# KA2_5.net
KiCad netlist of a schematic drawn in Altium Designer
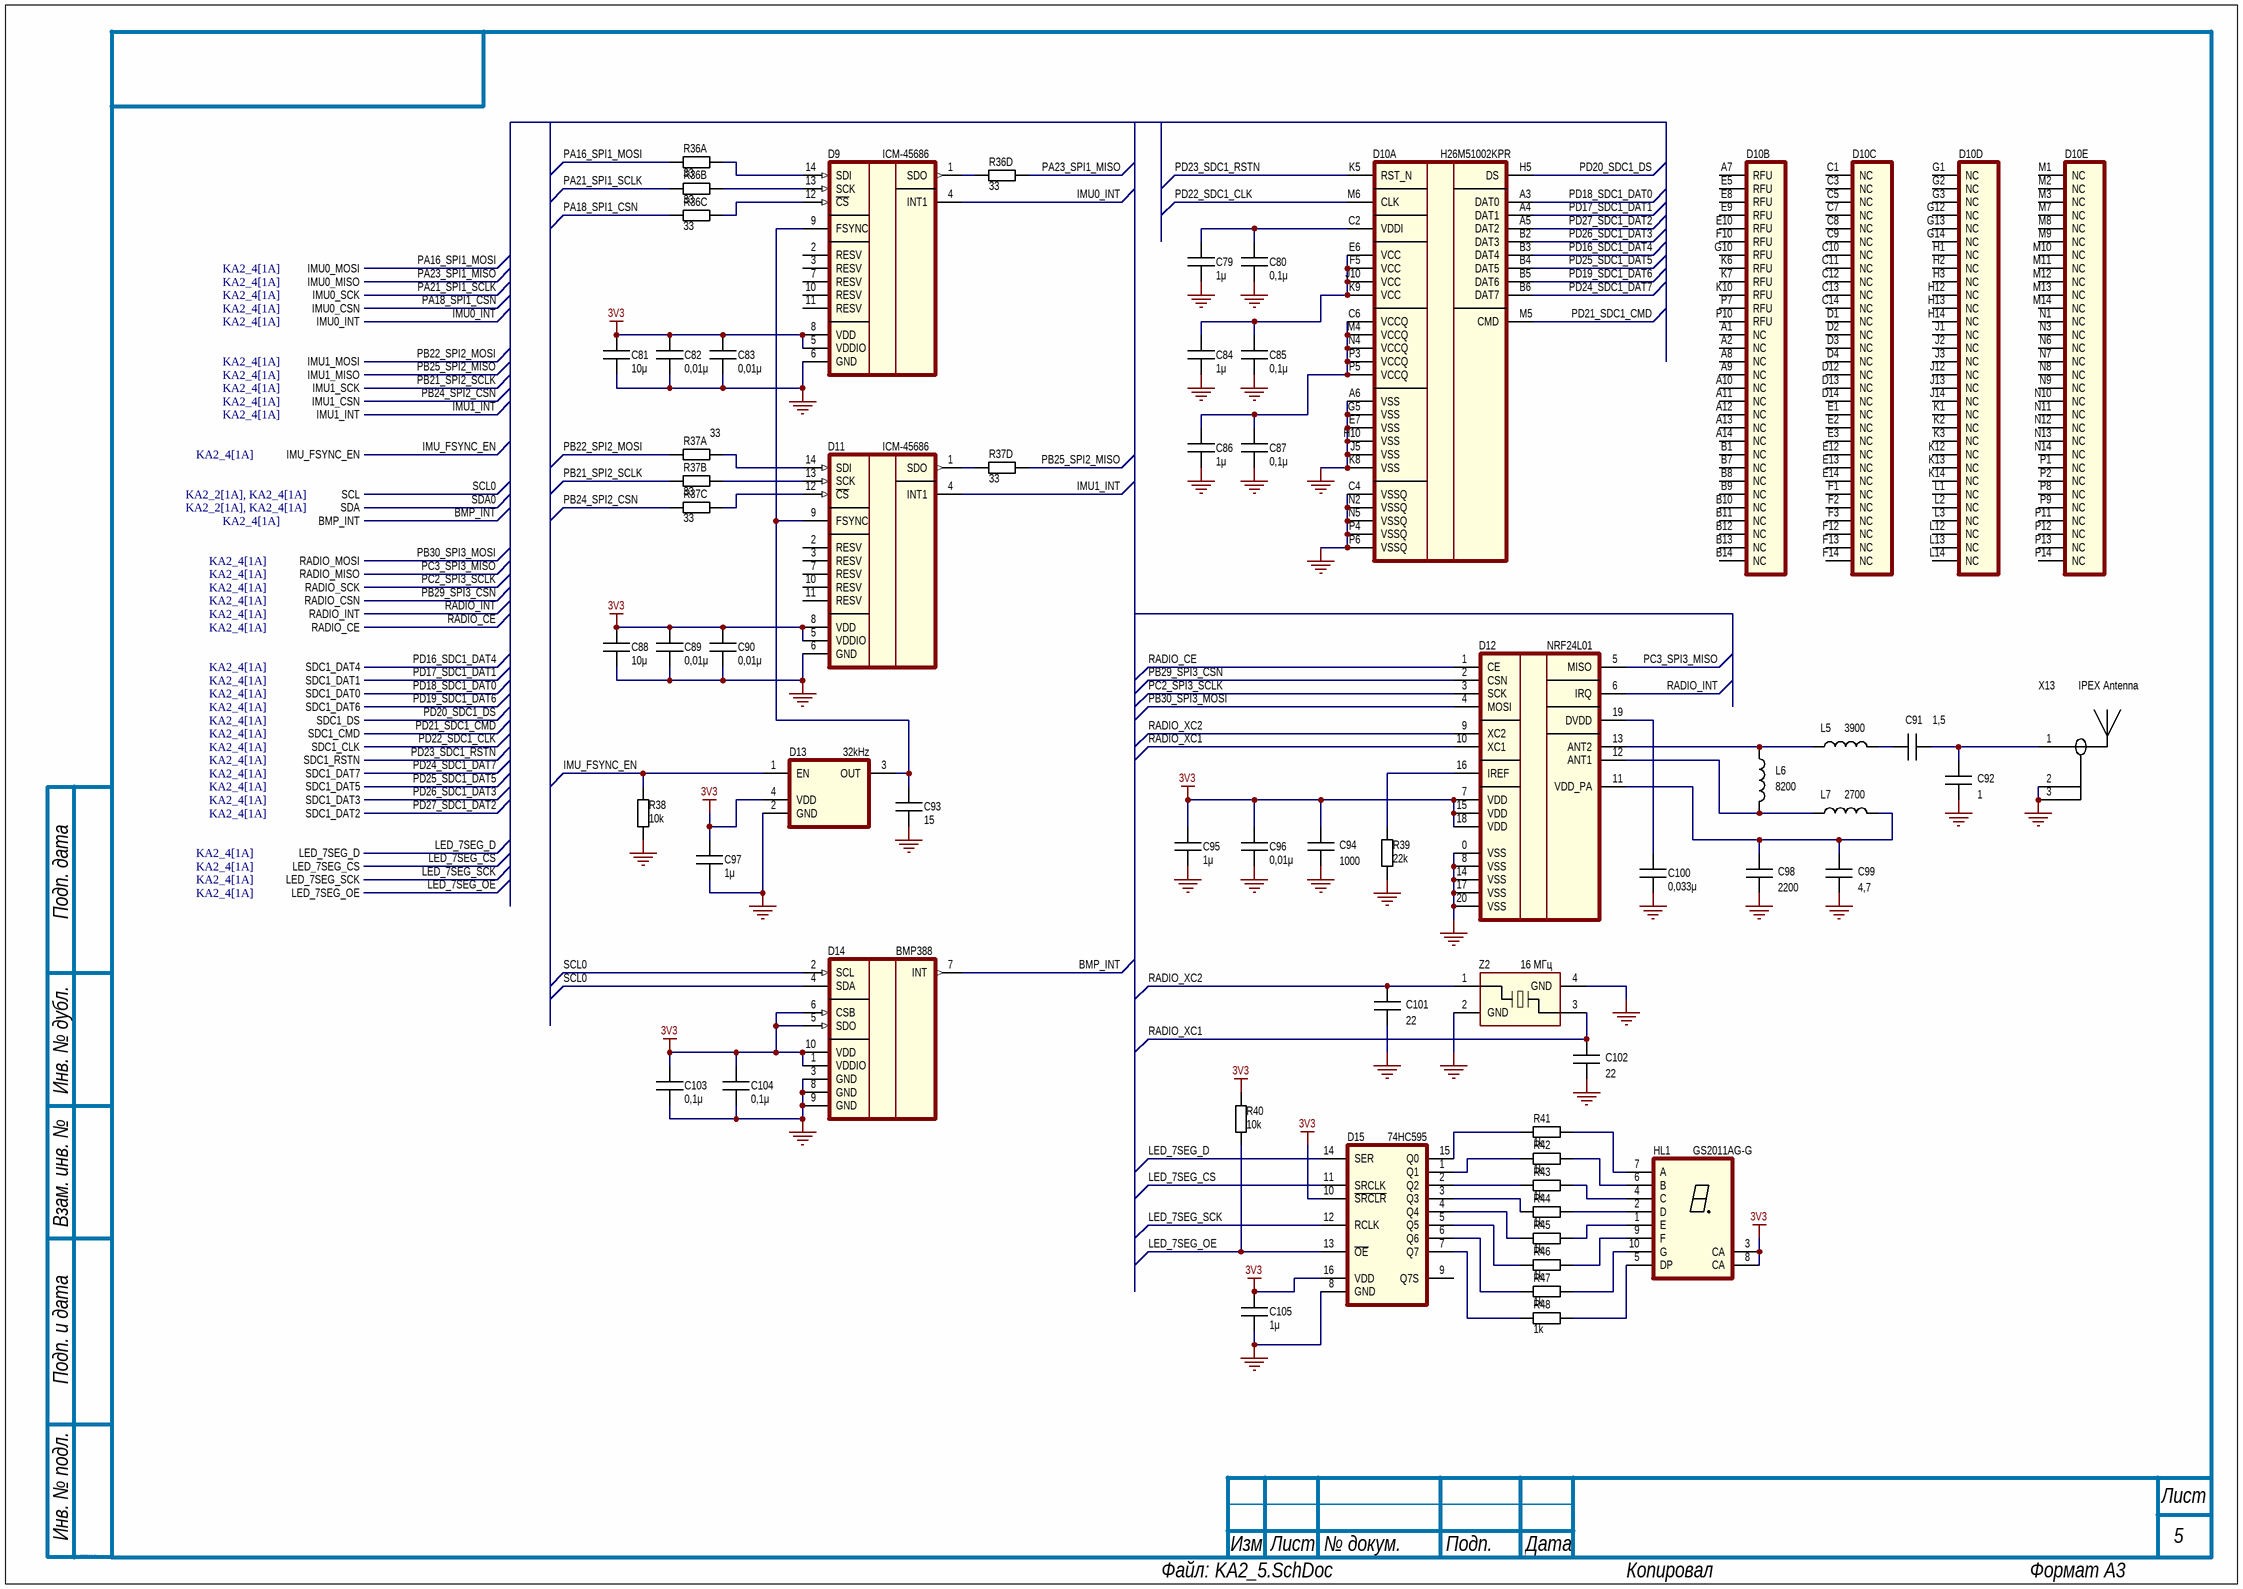
[diagram p0: KA2_5.SchDoc]

(export (version "E")
  (design (tool "Eeschema 10.0.6"))
  (components
    (comp (ref "C79")
      (value "1μ")
      (footprint "Capacitor_0402")
      (fields
        (field (name "VALUEMANUFACTURERPARTNUMBER") "Ceramic capacitor, 1μ, X7R, ±10%, 16V, 0402")
        (field (name "TOLERANCE") "±10%")
        (field (name "VOLTAGE") "16V")
      )
      (libsource (lib "Barsotion") (part "Ceramic_0402"))
    )
    (comp (ref "C80")
      (value "0,1μ")
      (footprint "Capacitor_0402")
      (fields
        (field (name "VALUEMANUFACTURERPARTNUMBER") "Ceramic capacitor, 0,1μ, X7R, ±10%, 16V, 0402")
        (field (name "TOLERANCE") "±10%")
        (field (name "VOLTAGE") "16V")
      )
      (libsource (lib "Barsotion") (part "Ceramic_0402"))
    )
    (comp (ref "C81")
      (value "10μ")
      (footprint "Capacitor_0402")
      (fields
        (field (name "VALUEMANUFACTURERPARTNUMBER") "Ceramic capacitor, 10μ, X7R, ±10%, 16V, 0402")
        (field (name "TOLERANCE") "±10%")
        (field (name "VOLTAGE") "16V")
      )
      (libsource (lib "Barsotion") (part "Ceramic_0402"))
    )
    (comp (ref "C82")
      (value "0,01μ")
      (footprint "Capacitor_0402")
      (fields
        (field (name "VALUEMANUFACTURERPARTNUMBER") "Ceramic capacitor, 0,01μ, X7R, ±10%, 16V, 0402")
        (field (name "TOLERANCE") "±10%")
        (field (name "VOLTAGE") "16V")
      )
      (libsource (lib "Barsotion") (part "Ceramic_0402"))
    )
    (comp (ref "C83")
      (value "0,01μ")
      (footprint "Capacitor_0402")
      (fields
        (field (name "VALUEMANUFACTURERPARTNUMBER") "Ceramic capacitor, 0,01μ, X7R, ±10%, 16V, 0402")
        (field (name "TOLERANCE") "±10%")
        (field (name "VOLTAGE") "16V")
      )
      (libsource (lib "Barsotion") (part "Ceramic_0402"))
    )
    (comp (ref "C84")
      (value "1μ")
      (footprint "Capacitor_0402")
      (fields
        (field (name "VALUEMANUFACTURERPARTNUMBER") "Ceramic capacitor, 1μ, X7R, ±10%, 16V, 0402")
        (field (name "TOLERANCE") "±10%")
        (field (name "VOLTAGE") "16V")
      )
      (libsource (lib "Barsotion") (part "Ceramic_0402"))
    )
    (comp (ref "C85")
      (value "0,1μ")
      (footprint "Capacitor_0402")
      (fields
        (field (name "VALUEMANUFACTURERPARTNUMBER") "Ceramic capacitor, 0,1μ, X7R, ±10%, 16V, 0402")
        (field (name "TOLERANCE") "±10%")
        (field (name "VOLTAGE") "16V")
      )
      (libsource (lib "Barsotion") (part "Ceramic_0402"))
    )
    (comp (ref "C86")
      (value "1μ")
      (footprint "Capacitor_0402")
      (fields
        (field (name "VALUEMANUFACTURERPARTNUMBER") "Ceramic capacitor, 1μ, X7R, ±10%, 16V, 0402")
        (field (name "TOLERANCE") "±10%")
        (field (name "VOLTAGE") "16V")
      )
      (libsource (lib "Barsotion") (part "Ceramic_0402"))
    )
    (comp (ref "C87")
      (value "0,1μ")
      (footprint "Capacitor_0402")
      (fields
        (field (name "VALUEMANUFACTURERPARTNUMBER") "Ceramic capacitor, 0,1μ, X7R, ±10%, 16V, 0402")
        (field (name "TOLERANCE") "±10%")
        (field (name "VOLTAGE") "16V")
      )
      (libsource (lib "Barsotion") (part "Ceramic_0402"))
    )
    (comp (ref "C88")
      (value "10μ")
      (footprint "Capacitor_0402")
      (fields
        (field (name "VALUEMANUFACTURERPARTNUMBER") "Ceramic capacitor, 10μ, X7R, ±10%, 16V, 0402")
        (field (name "TOLERANCE") "±10%")
        (field (name "VOLTAGE") "16V")
      )
      (libsource (lib "Barsotion") (part "Ceramic_0402"))
    )
    (comp (ref "C89")
      (value "0,01μ")
      (footprint "Capacitor_0402")
      (fields
        (field (name "VALUEMANUFACTURERPARTNUMBER") "Ceramic capacitor, 0,01μ, X7R, ±10%, 16V, 0402")
        (field (name "TOLERANCE") "±10%")
        (field (name "VOLTAGE") "16V")
      )
      (libsource (lib "Barsotion") (part "Ceramic_0402"))
    )
    (comp (ref "C90")
      (value "0,01μ")
      (footprint "Capacitor_0402")
      (fields
        (field (name "VALUEMANUFACTURERPARTNUMBER") "Ceramic capacitor, 0,01μ, X7R, ±10%, 16V, 0402")
        (field (name "TOLERANCE") "±10%")
        (field (name "VOLTAGE") "16V")
      )
      (libsource (lib "Barsotion") (part "Ceramic_0402"))
    )
    (comp (ref "C91")
      (value "1,5")
      (footprint "Capacitor_0402")
      (fields
        (field (name "VALUEMANUFACTURERPARTNUMBER") "Ceramic capacitor, 1,5, X7R, ±10%, 16V, 0402")
        (field (name "TOLERANCE") "±10%")
        (field (name "VOLTAGE") "16V")
      )
      (libsource (lib "Barsotion") (part "Ceramic_0402"))
    )
    (comp (ref "C92")
      (value "1")
      (footprint "Capacitor_0402")
      (fields
        (field (name "VALUEMANUFACTURERPARTNUMBER") "Ceramic capacitor, 1, X7R, ±10%, 16V, 0402")
        (field (name "TOLERANCE") "±10%")
        (field (name "VOLTAGE") "16V")
      )
      (libsource (lib "Barsotion") (part "Ceramic_0402"))
    )
    (comp (ref "C93")
      (value "15")
      (footprint "Capacitor_0402")
      (fields
        (field (name "VALUEMANUFACTURERPARTNUMBER") "Ceramic capacitor, 15, X7R, ±10%, 16V, 0402")
        (field (name "TOLERANCE") "±10%")
        (field (name "VOLTAGE") "16V")
      )
      (libsource (lib "Barsotion") (part "Ceramic_0402"))
    )
    (comp (ref "C94")
      (value "1000")
      (footprint "Capacitor_0402")
      (fields
        (field (name "VALUEMANUFACTURERPARTNUMBER") "Ceramic capacitor, 1000, X7R, ±10%, 16V, 0402")
        (field (name "TOLERANCE") "±10%")
        (field (name "VOLTAGE") "16V")
      )
      (libsource (lib "Barsotion") (part "Ceramic_0402"))
    )
    (comp (ref "C95")
      (value "1μ")
      (footprint "Capacitor_0402")
      (fields
        (field (name "VALUEMANUFACTURERPARTNUMBER") "Ceramic capacitor, 1μ, X7R, ±10%, 16V, 0402")
        (field (name "TOLERANCE") "±10%")
        (field (name "VOLTAGE") "16V")
      )
      (libsource (lib "Barsotion") (part "Ceramic_0402"))
    )
    (comp (ref "C96")
      (value "0,01μ")
      (footprint "Capacitor_0402")
      (fields
        (field (name "VALUEMANUFACTURERPARTNUMBER") "Ceramic capacitor, 0,01μ, X7R, ±10%, 16V, 0402")
        (field (name "TOLERANCE") "±10%")
        (field (name "VOLTAGE") "16V")
      )
      (libsource (lib "Barsotion") (part "Ceramic_0402"))
    )
    (comp (ref "C97")
      (value "1μ")
      (footprint "Capacitor_0402")
      (fields
        (field (name "VALUEMANUFACTURERPARTNUMBER") "Ceramic capacitor, 1μ, X7R, ±10%, 16V, 0402")
        (field (name "TOLERANCE") "±10%")
        (field (name "VOLTAGE") "16V")
      )
      (libsource (lib "Barsotion") (part "Ceramic_0402"))
    )
    (comp (ref "C98")
      (value "2200")
      (footprint "Capacitor_0402")
      (fields
        (field (name "VALUEMANUFACTURERPARTNUMBER") "Ceramic capacitor, 2200, X7R, ±10%, 16V, 0402")
        (field (name "TOLERANCE") "±10%")
        (field (name "VOLTAGE") "16V")
      )
      (libsource (lib "Barsotion") (part "Ceramic_0402"))
    )
    (comp (ref "C99")
      (value "4,7")
      (footprint "Capacitor_0402")
      (fields
        (field (name "VALUEMANUFACTURERPARTNUMBER") "Ceramic capacitor, 4,7, X7R, ±10%, 16V, 0402")
        (field (name "TOLERANCE") "±10%")
        (field (name "VOLTAGE") "16V")
      )
      (libsource (lib "Barsotion") (part "Ceramic_0402"))
    )
    (comp (ref "C100")
      (value "0,033μ")
      (footprint "Capacitor_0402")
      (fields
        (field (name "VALUEMANUFACTURERPARTNUMBER") "Ceramic capacitor, 0,033μ, X7R, ±10%, 16V, 0402")
        (field (name "TOLERANCE") "±10%")
        (field (name "VOLTAGE") "16V")
      )
      (libsource (lib "Barsotion") (part "Ceramic_0402"))
    )
    (comp (ref "C101")
      (value "22")
      (footprint "Capacitor_0402")
      (fields
        (field (name "VALUEMANUFACTURERPARTNUMBER") "Ceramic capacitor, 22, X7R, ±10%, 16V, 0402")
        (field (name "TOLERANCE") "±10%")
        (field (name "VOLTAGE") "16V")
      )
      (libsource (lib "Barsotion") (part "Ceramic_0402"))
    )
    (comp (ref "C102")
      (value "22")
      (footprint "Capacitor_0402")
      (fields
        (field (name "VALUEMANUFACTURERPARTNUMBER") "Ceramic capacitor, 22, X7R, ±10%, 16V, 0402")
        (field (name "TOLERANCE") "±10%")
        (field (name "VOLTAGE") "16V")
      )
      (libsource (lib "Barsotion") (part "Ceramic_0402"))
    )
    (comp (ref "C103")
      (value "0,1μ")
      (footprint "Capacitor_0402")
      (fields
        (field (name "VALUEMANUFACTURERPARTNUMBER") "Ceramic capacitor, 0,1μ, X7R, ±10%, 16V, 0402")
        (field (name "TOLERANCE") "±10%")
        (field (name "VOLTAGE") "16V")
      )
      (libsource (lib "Barsotion") (part "Ceramic_0402"))
    )
    (comp (ref "C104")
      (value "0,1μ")
      (footprint "Capacitor_0402")
      (fields
        (field (name "VALUEMANUFACTURERPARTNUMBER") "Ceramic capacitor, 0,1μ, X7R, ±10%, 16V, 0402")
        (field (name "TOLERANCE") "±10%")
        (field (name "VOLTAGE") "16V")
      )
      (libsource (lib "Barsotion") (part "Ceramic_0402"))
    )
    (comp (ref "C105")
      (value "1μ")
      (footprint "Capacitor_0402")
      (fields
        (field (name "VALUEMANUFACTURERPARTNUMBER") "Ceramic capacitor, 1μ, X7R, ±10%, 16V, 0402")
        (field (name "TOLERANCE") "±10%")
        (field (name "VOLTAGE") "16V")
      )
      (libsource (lib "Barsotion") (part "Ceramic_0402"))
    )
    (comp (ref "D9")
      (value "ICM-45686")
      (footprint "ICM-42688-P_LGA-14_3x2.5mm")
      (description "Микросхема интегрального гироскопа-акселерометра (IMU), LGA-14 3x2.5mm")
      (fields (field (name "MANUFACTURER") "TDK InvenSense"))
      (libsource (lib "Barsotion") (part "ICM-45686"))
    )
    (comp (ref "D10")
      (value "H26M51002KPR")
      (footprint "eMMC_13x11.5mm")
      (description "Микросхема eMMC, 16ГБ, FBGA-153 13x11.5mm")
      (fields
        (field (name "MANUFACTURER") "HYNIX")
        (field (name "Comment") "16GB eMMC 5.1 FBGA-153 Memory (ICs) RoHS")
        (field (name "MFR.PART") "H26M51002KPR")
      )
      (libsource (lib "Barsotion") (part "eMMC_H26M51002KPR"))
    )
    (comp (ref "D11")
      (value "ICM-45686")
      (footprint "ICM-42688-P_LGA-14_3x2.5mm")
      (description "Микросхема интегрального гироскопа-акселерометра (IMU), LGA-14 3x2.5mm")
      (fields (field (name "MANUFACTURER") "TDK InvenSense"))
      (libsource (lib "Barsotion") (part "ICM-45686"))
    )
    (comp (ref "D12")
      (value "NRF24L01")
      (footprint "QFN-20_4x4mm")
      (description "Микросхема радио-приемопередатчика 2.4 ГГц, QFN-20 4x4mm")
      (fields (field (name "MFR.PART") "NRF24L01P-R") (field (name "MANUFACTURER") "Nordic Semicomductor"))
      (libsource (lib "Barsotion") (part "NRF24L01P-R"))
    )
    (comp (ref "D13")
      (value "32kHz")
      (footprint "OSC: 2016")
      (description "Кварцевый генератор 32,768 кГц, 2016, 10ppm")
      (fields
        (field (name "MFR.PART") "OK7EL89CJI-111YLC-32.768K")
        (field (name "MANUFACTURER") "YXC Crystal Oscillators")
      )
      (libsource (lib "Barsotion") (part "OK7EL89CJI-111YLC-32.768K"))
    )
    (comp (ref "D14")
      (value "BMP388")
      (footprint "BMP388_LGA-10_2x2mm")
      (description "Микросхема интегрального барометра, LGA-10 2x2mm")
      (fields (field (name "MANUFACTURER") "Bosch"))
      (libsource (lib "Barsotion") (part "BMP388"))
    )
    (comp (ref "D15")
      (value "74HC595")
      (footprint "TSSOP-16")
      (description "Микросхема восьмиразрядного сдвигового регистра")
      (fields (field (name "MANUFACTURER") "Texas Instruments") (field (name "MFR.PART") "SN74HC595PWR"))
      (libsource (lib "Barsotion") (part "SN74HC595PWR"))
    )
    (comp (ref "HL1")
      (value "GS2011AG-G")
      (footprint "LED_7SEG_SMD")
      (description "Индикатор светодиодный семисегментный зеленый, SMD, 10x6.9 мм, общий анод")
      (fields (field (name "MANUFACTURER") "Guangcai Display") (field (name "MFR.PART") "GS2011AG-G"))
      (libsource (lib "Barsotion") (part "GS2011AG-G"))
    )
    (comp (ref "L5")
      (value "3900")
      (footprint "IND: 0402")
      (fields
        (field (name "VALUEMANUFACTURERPARTNUMBER") "Inductor, 3900, ±10%, 0402")
        (field (name "TOLERANCE") "±10%")
      )
      (libsource (lib "Barsotion") (part "Inductor_0402"))
    )
    (comp (ref "L6")
      (value "8200")
      (footprint "IND: 0402")
      (fields
        (field (name "VALUEMANUFACTURERPARTNUMBER") "Inductor, 8200, ±10%, 0402")
        (field (name "TOLERANCE") "±10%")
      )
      (libsource (lib "Barsotion") (part "Inductor_0402"))
    )
    (comp (ref "L7")
      (value "2700")
      (footprint "IND: 0402")
      (fields
        (field (name "VALUEMANUFACTURERPARTNUMBER") "Inductor, 2700, ±10%, 0402")
        (field (name "TOLERANCE") "±10%")
      )
      (libsource (lib "Barsotion") (part "Inductor_0402"))
    )
    (comp (ref "R36")
      (value "33")
      (footprint "Resistor:RES: Array 4x0402")
      (fields
        (field (name "VALUEMANUFACTURERPARTNUMBER") "Resistor array (4), 33, ±1%, 0402")
        (field (name "TOLERANCE") "±1%")
      )
      (libsource (lib "Barsotion") (part "ResistorArray_0402_4"))
    )
    (comp (ref "R37")
      (value "33")
      (footprint "Resistor:RES: Array 4x0402")
      (fields
        (field (name "VALUEMANUFACTURERPARTNUMBER") "Resistor array (4), 33, ±1%, 0402")
        (field (name "TOLERANCE") "±1%")
      )
      (libsource (lib "Barsotion") (part "ResistorArray_0402_4"))
    )
    (comp (ref "R38")
      (value "10k")
      (footprint "RES: 0402")
      (fields
        (field (name "VALUEMANUFACTURERPARTNUMBER") "Resistor, 10k, ±1%, 0402")
        (field (name "TOLERANCE") "±1%")
      )
      (libsource (lib "") (part "Resistor_0402_1"))
    )
    (comp (ref "R39")
      (value "22k")
      (footprint "RES: 0402")
      (fields
        (field (name "VALUEMANUFACTURERPARTNUMBER") "Resistor, 22k, ±1%, 0402")
        (field (name "TOLERANCE") "±1%")
      )
      (libsource (lib "") (part "Resistor_0402_1"))
    )
    (comp (ref "R40")
      (value "10k")
      (footprint "RES: 0402")
      (fields
        (field (name "VALUEMANUFACTURERPARTNUMBER") "Resistor, 10k, ±1%, 0402")
        (field (name "TOLERANCE") "±1%")
      )
      (libsource (lib "") (part "Resistor_0402_1"))
    )
    (comp (ref "R41")
      (value "1k")
      (footprint "RES: 0402")
      (fields
        (field (name "VALUEMANUFACTURERPARTNUMBER") "Resistor, 1k, ±1%, 0402")
        (field (name "TOLERANCE") "±1%")
      )
      (libsource (lib "Barsotion") (part "Resistor_0402"))
    )
    (comp (ref "R42")
      (value "1k")
      (footprint "RES: 0402")
      (fields
        (field (name "VALUEMANUFACTURERPARTNUMBER") "Resistor, 1k, ±1%, 0402")
        (field (name "TOLERANCE") "±1%")
      )
      (libsource (lib "Barsotion") (part "Resistor_0402"))
    )
    (comp (ref "R43")
      (value "1k")
      (footprint "RES: 0402")
      (fields
        (field (name "VALUEMANUFACTURERPARTNUMBER") "Resistor, 1k, ±1%, 0402")
        (field (name "TOLERANCE") "±1%")
      )
      (libsource (lib "Barsotion") (part "Resistor_0402"))
    )
    (comp (ref "R44")
      (value "1k")
      (footprint "RES: 0402")
      (fields
        (field (name "VALUEMANUFACTURERPARTNUMBER") "Resistor, 1k, ±1%, 0402")
        (field (name "TOLERANCE") "±1%")
      )
      (libsource (lib "Barsotion") (part "Resistor_0402"))
    )
    (comp (ref "R45")
      (value "1k")
      (footprint "RES: 0402")
      (fields
        (field (name "VALUEMANUFACTURERPARTNUMBER") "Resistor, 1k, ±1%, 0402")
        (field (name "TOLERANCE") "±1%")
      )
      (libsource (lib "Barsotion") (part "Resistor_0402"))
    )
    (comp (ref "R46")
      (value "1k")
      (footprint "RES: 0402")
      (fields
        (field (name "VALUEMANUFACTURERPARTNUMBER") "Resistor, 1k, ±1%, 0402")
        (field (name "TOLERANCE") "±1%")
      )
      (libsource (lib "Barsotion") (part "Resistor_0402"))
    )
    (comp (ref "R47")
      (value "1k")
      (footprint "RES: 0402")
      (fields
        (field (name "VALUEMANUFACTURERPARTNUMBER") "Resistor, 1k, ±1%, 0402")
        (field (name "TOLERANCE") "±1%")
      )
      (libsource (lib "Barsotion") (part "Resistor_0402"))
    )
    (comp (ref "R48")
      (value "1k")
      (footprint "RES: 0402")
      (fields
        (field (name "VALUEMANUFACTURERPARTNUMBER") "Resistor, 1k, ±1%, 0402")
        (field (name "TOLERANCE") "±1%")
      )
      (libsource (lib "Barsotion") (part "Resistor_0402"))
    )
    (comp (ref "X13")
      (value "IPEX Antenna")
      (footprint "Conn_IPEX_ANTENNA")
      (description "Connector Receptacle IPEX Male Pin 50Ω Surface Mount")
      (fields (field (name "MANUFACTURER") "HRS") (field (name "MFR.PART") "U.FL-R-SMT-1(80)"))
      (libsource (lib "Barsotion") (part "Antenna_IPEX"))
    )
    (comp (ref "Z2")
      (value "16 МГц")
      (footprint "OSC: 2016")
      (description "Кварцевый резонатор 16 МГц 2016")
      (fields
        (field (name "MFR.PART") "XL7EL89COI-111YLC-16M")
        (field (name "MANUFACTURER") "YXC Crystal Oscillators")
      )
      (libsource (lib "Barsotion") (part "Crystal_XL7EL89COI-111YLC-16M"))
    )
  )
  (nets
    (net (code "1") (name "/BMP_INT") (class "Default")
      (node (ref "D14") (pin "7") (pinfunction "INT_7") (pintype "output"))
    )
    (net (code "2") (name "/IMU0_INT") (class "Default")
      (node (ref "D9") (pin "4") (pinfunction "INT1_4") (pintype "passive"))
    )
    (net (code "3") (name "/IMU1_INT") (class "Default")
      (node (ref "D11") (pin "4") (pinfunction "INT1_4") (pintype "passive"))
    )
    (net (code "4") (name "/IMU_FSYNC_EN") (class "Default")
      (node (ref "D13") (pin "1") (pinfunction "EN_1") (pintype "passive"))
      (node (ref "R38") (pin "2") (pinfunction "2_2") (pintype "passive"))
    )
    (net (code "5") (name "/LED_7SEG_CS") (class "Default")
      (node (ref "D15") (pin "11") (pinfunction "SRCLK_11") (pintype "passive"))
    )
    (net (code "6") (name "/LED_7SEG_D") (class "Default")
      (node (ref "D15") (pin "14") (pinfunction "SER_14") (pintype "passive"))
    )
    (net (code "7") (name "/LED_7SEG_OE") (class "Default")
      (node (ref "D15") (pin "13") (pinfunction "~{OE}_13") (pintype "passive"))
      (node (ref "R40") (pin "1") (pinfunction "1_1") (pintype "passive"))
    )
    (net (code "8") (name "/LED_7SEG_SCK") (class "Default")
      (node (ref "D15") (pin "12") (pinfunction "RCLK_12") (pintype "passive"))
    )
    (net (code "9") (name "/PA16_SPI1_MOSI") (class "Default")
      (node (ref "R36") (pin "1") (pinfunction "1_1") (pintype "passive"))
    )
    (net (code "10") (name "/PA18_SPI1_CSN") (class "Default")
      (node (ref "R36") (pin "3") (pinfunction "3_3") (pintype "passive"))
    )
    (net (code "11") (name "/PA21_SPI1_SCLK") (class "Default")
      (node (ref "R36") (pin "2") (pinfunction "2_2") (pintype "passive"))
    )
    (net (code "12") (name "/PA23_SPI1_MISO") (class "Default")
      (node (ref "R36") (pin "5") (pinfunction "5_5") (pintype "passive"))
    )
    (net (code "13") (name "/PB21_SPI2_SCLK") (class "Default")
      (node (ref "R37") (pin "2") (pinfunction "2_2") (pintype "passive"))
    )
    (net (code "14") (name "/PB22_SPI2_MOSI") (class "Default")
      (node (ref "R37") (pin "1") (pinfunction "1_1") (pintype "passive"))
    )
    (net (code "15") (name "/PB24_SPI2_CSN") (class "Default")
      (node (ref "R37") (pin "3") (pinfunction "3_3") (pintype "passive"))
    )
    (net (code "16") (name "/PB25_SPI2_MISO") (class "Default")
      (node (ref "R37") (pin "5") (pinfunction "5_5") (pintype "passive"))
    )
    (net (code "17") (name "/PB29_SPI3_CSN") (class "Default")
      (node (ref "D12") (pin "2") (pinfunction "CSN_2") (pintype "passive"))
    )
    (net (code "18") (name "/PB30_SPI3_MOSI") (class "Default")
      (node (ref "D12") (pin "4") (pinfunction "MOSI_4") (pintype "passive"))
    )
    (net (code "19") (name "/PC2_SPI3_SCLK") (class "Default")
      (node (ref "D12") (pin "3") (pinfunction "SCK_3") (pintype "passive"))
    )
    (net (code "20") (name "/PC3_SPI3_MISO") (class "Default")
      (node (ref "D12") (pin "5") (pinfunction "MISO_5") (pintype "passive"))
    )
    (net (code "21") (name "/PD16_SDC1_DAT4") (class "Default")
      (node (ref "D10") (pin "B3") (pinfunction "DAT4_B3") (pintype "passive"))
    )
    (net (code "22") (name "/PD17_SDC1_DAT1") (class "Default")
      (node (ref "D10") (pin "A4") (pinfunction "DAT1_A4") (pintype "passive"))
    )
    (net (code "23") (name "/PD18_SDC1_DAT0") (class "Default")
      (node (ref "D10") (pin "A3") (pinfunction "DAT0_A3") (pintype "passive"))
    )
    (net (code "24") (name "/PD19_SDC1_DAT6") (class "Default")
      (node (ref "D10") (pin "B5") (pinfunction "DAT6_B5") (pintype "passive"))
    )
    (net (code "25") (name "/PD20_SDC1_DS") (class "Default")
      (node (ref "D10") (pin "H5") (pinfunction "DS_H5") (pintype "passive"))
    )
    (net (code "26") (name "/PD21_SDC1_CMD") (class "Default")
      (node (ref "D10") (pin "M5") (pinfunction "CMD_M5") (pintype "passive"))
    )
    (net (code "27") (name "/PD22_SDC1_CLK") (class "Default")
      (node (ref "D10") (pin "M6") (pinfunction "CLK_M6") (pintype "passive"))
    )
    (net (code "28") (name "/PD23_SDC1_RSTN") (class "Default")
      (node (ref "D10") (pin "K5") (pinfunction "RST_N_K5") (pintype "passive"))
    )
    (net (code "29") (name "/PD24_SDC1_DAT7") (class "Default")
      (node (ref "D10") (pin "B6") (pinfunction "DAT7_B6") (pintype "passive"))
    )
    (net (code "30") (name "/PD25_SDC1_DAT5") (class "Default")
      (node (ref "D10") (pin "B4") (pinfunction "DAT5_B4") (pintype "passive"))
    )
    (net (code "31") (name "/PD26_SDC1_DAT3") (class "Default")
      (node (ref "D10") (pin "B2") (pinfunction "DAT3_B2") (pintype "passive"))
    )
    (net (code "32") (name "/PD27_SDC1_DAT2") (class "Default")
      (node (ref "D10") (pin "A5") (pinfunction "DAT2_A5") (pintype "passive"))
    )
    (net (code "33") (name "/RADIO_CE") (class "Default")
      (node (ref "D12") (pin "1") (pinfunction "CE_1") (pintype "passive"))
    )
    (net (code "34") (name "/RADIO_INT") (class "Default")
      (node (ref "D12") (pin "6") (pinfunction "IRQ_6") (pintype "passive"))
    )
    (net (code "35") (name "/RADIO_XC1") (class "Default")
      (node (ref "C102") (pin "1") (pinfunction "1_1") (pintype "passive"))
      (node (ref "D12") (pin "10") (pinfunction "XC1_10") (pintype "passive"))
      (node (ref "Z2") (pin "3") (pinfunction "X2_3") (pintype "passive"))
    )
    (net (code "36") (name "/RADIO_XC2") (class "Default")
      (node (ref "C101") (pin "1") (pinfunction "1_1") (pintype "passive"))
      (node (ref "D12") (pin "9") (pinfunction "XC2_9") (pintype "passive"))
      (node (ref "Z2") (pin "1") (pinfunction "X1_1") (pintype "passive"))
    )
    (net (code "37") (name "/SCL0") (class "Default")
      (node (ref "D14") (pin "2") (pinfunction "SCL_2") (pintype "input"))
      (node (ref "D14") (pin "4") (pinfunction "SDA_4") (pintype "open_collector"))
    )
    (net (code "39") (name "3V3") (class "Default")
      (node (ref "C103") (pin "2") (pinfunction "2_2") (pintype "passive"))
      (node (ref "C104") (pin "2") (pinfunction "2_2") (pintype "passive"))
      (node (ref "C105") (pin "2") (pinfunction "2_2") (pintype "passive"))
      (node (ref "C81") (pin "2") (pinfunction "2_2") (pintype "passive"))
      (node (ref "C82") (pin "2") (pinfunction "2_2") (pintype "passive"))
      (node (ref "C83") (pin "2") (pinfunction "2_2") (pintype "passive"))
      (node (ref "C88") (pin "2") (pinfunction "2_2") (pintype "passive"))
      (node (ref "C89") (pin "2") (pinfunction "2_2") (pintype "passive"))
      (node (ref "C90") (pin "2") (pinfunction "2_2") (pintype "passive"))
      (node (ref "C94") (pin "1") (pinfunction "1_1") (pintype "passive"))
      (node (ref "C95") (pin "2") (pinfunction "2_2") (pintype "passive"))
      (node (ref "C96") (pin "2") (pinfunction "2_2") (pintype "passive"))
      (node (ref "C97") (pin "2") (pinfunction "2_2") (pintype "passive"))
      (node (ref "D11") (pin "5") (pinfunction "VDDIO_5") (pintype "power_in"))
      (node (ref "D11") (pin "8") (pinfunction "VDD_8") (pintype "power_in"))
      (node (ref "D12") (pin "15") (pinfunction "VDD_15") (pintype "passive"))
      (node (ref "D12") (pin "18") (pinfunction "VDD_18") (pintype "passive"))
      (node (ref "D12") (pin "7") (pinfunction "VDD_7") (pintype "passive"))
      (node (ref "D13") (pin "4") (pinfunction "VDD_4") (pintype "passive"))
      (node (ref "D14") (pin "1") (pinfunction "VDDIO_1") (pintype "power_in"))
      (node (ref "D14") (pin "10") (pinfunction "VDD_10") (pintype "power_in"))
      (node (ref "D14") (pin "5") (pinfunction "SDO_5") (pintype "input"))
      (node (ref "D14") (pin "6") (pinfunction "CSB_6") (pintype "input"))
      (node (ref "D15") (pin "10") (pinfunction "~{SRCLR}_10") (pintype "passive"))
      (node (ref "D15") (pin "16") (pinfunction "VDD_16") (pintype "passive"))
      (node (ref "D9") (pin "5") (pinfunction "VDDIO_5") (pintype "power_in"))
      (node (ref "D9") (pin "8") (pinfunction "VDD_8") (pintype "power_in"))
      (node (ref "HL1") (pin "3") (pinfunction "CA_3") (pintype "passive"))
      (node (ref "HL1") (pin "8") (pinfunction "CA_8") (pintype "passive"))
      (node (ref "R40") (pin "2") (pinfunction "2_2") (pintype "passive"))
    )
    (net (code "40") (name "GND") (class "Default")
      (node (ref "C100") (pin "1") (pinfunction "1_1") (pintype "passive"))
      (node (ref "C101") (pin "2") (pinfunction "2_2") (pintype "passive"))
      (node (ref "C102") (pin "2") (pinfunction "2_2") (pintype "passive"))
      (node (ref "C103") (pin "1") (pinfunction "1_1") (pintype "passive"))
      (node (ref "C104") (pin "1") (pinfunction "1_1") (pintype "passive"))
      (node (ref "C105") (pin "1") (pinfunction "1_1") (pintype "passive"))
      (node (ref "C79") (pin "1") (pinfunction "1_1") (pintype "passive"))
      (node (ref "C80") (pin "1") (pinfunction "1_1") (pintype "passive"))
      (node (ref "C81") (pin "1") (pinfunction "1_1") (pintype "passive"))
      (node (ref "C82") (pin "1") (pinfunction "1_1") (pintype "passive"))
      (node (ref "C83") (pin "1") (pinfunction "1_1") (pintype "passive"))
      (node (ref "C84") (pin "1") (pinfunction "1_1") (pintype "passive"))
      (node (ref "C85") (pin "1") (pinfunction "1_1") (pintype "passive"))
      (node (ref "C86") (pin "1") (pinfunction "1_1") (pintype "passive"))
      (node (ref "C87") (pin "1") (pinfunction "1_1") (pintype "passive"))
      (node (ref "C88") (pin "1") (pinfunction "1_1") (pintype "passive"))
      (node (ref "C89") (pin "1") (pinfunction "1_1") (pintype "passive"))
      (node (ref "C90") (pin "1") (pinfunction "1_1") (pintype "passive"))
      (node (ref "C92") (pin "2") (pinfunction "2_2") (pintype "passive"))
      (node (ref "C93") (pin "1") (pinfunction "1_1") (pintype "passive"))
      (node (ref "C94") (pin "2") (pinfunction "2_2") (pintype "passive"))
      (node (ref "C95") (pin "1") (pinfunction "1_1") (pintype "passive"))
      (node (ref "C96") (pin "1") (pinfunction "1_1") (pintype "passive"))
      (node (ref "C97") (pin "1") (pinfunction "1_1") (pintype "passive"))
      (node (ref "C98") (pin "2") (pinfunction "2_2") (pintype "passive"))
      (node (ref "C99") (pin "2") (pinfunction "2_2") (pintype "passive"))
      (node (ref "D10") (pin "A6") (pinfunction "VSS_A6") (pintype "passive"))
      (node (ref "D10") (pin "C4") (pinfunction "VSSQ_C4") (pintype "passive"))
      (node (ref "D10") (pin "E7") (pinfunction "VSS_E7") (pintype "passive"))
      (node (ref "D10") (pin "G5") (pinfunction "VSS_G5") (pintype "passive"))
      (node (ref "D10") (pin "H10") (pinfunction "VSS_H10") (pintype "passive"))
      (node (ref "D10") (pin "J5") (pinfunction "VSS_J5") (pintype "passive"))
      (node (ref "D10") (pin "K8") (pinfunction "VSS_K8") (pintype "passive"))
      (node (ref "D10") (pin "N2") (pinfunction "VSSQ_N2") (pintype "passive"))
      (node (ref "D10") (pin "N5") (pinfunction "VSSQ_N5") (pintype "passive"))
      (node (ref "D10") (pin "P4") (pinfunction "VSSQ_P4") (pintype "passive"))
      (node (ref "D10") (pin "P6") (pinfunction "VSSQ_P6") (pintype "passive"))
      (node (ref "D11") (pin "6") (pinfunction "GND_6") (pintype "power_in"))
      (node (ref "D12") (pin "0") (pinfunction "VSS_0") (pintype "passive"))
      (node (ref "D12") (pin "14") (pinfunction "VSS_14") (pintype "passive"))
      (node (ref "D12") (pin "17") (pinfunction "VSS_17") (pintype "passive"))
      (node (ref "D12") (pin "20") (pinfunction "VSS_20") (pintype "passive"))
      (node (ref "D12") (pin "8") (pinfunction "VSS_8") (pintype "passive"))
      (node (ref "D13") (pin "2") (pinfunction "GND_2") (pintype "passive"))
      (node (ref "D14") (pin "3") (pinfunction "GND_3") (pintype "power_in"))
      (node (ref "D14") (pin "8") (pinfunction "GND_8") (pintype "power_in"))
      (node (ref "D14") (pin "9") (pinfunction "GND_9") (pintype "power_in"))
      (node (ref "D15") (pin "8") (pinfunction "GND_8") (pintype "passive"))
      (node (ref "D9") (pin "6") (pinfunction "GND_6") (pintype "power_in"))
      (node (ref "R38") (pin "1") (pinfunction "1_1") (pintype "passive"))
      (node (ref "R39") (pin "1") (pinfunction "1_1") (pintype "passive"))
      (node (ref "X13") (pin "2") (pinfunction "GND_2") (pintype "passive"))
      (node (ref "X13") (pin "3") (pinfunction "GND_3") (pintype "passive"))
      (node (ref "Z2") (pin "2") (pinfunction "GND_2") (pintype "passive"))
      (node (ref "Z2") (pin "4") (pinfunction "GND_4") (pintype "passive"))
    )
    (net (code "41") (name "Net-(C84-Pad2)") (class "Default")
      (node (ref "C84") (pin "2") (pinfunction "2_2") (pintype "passive"))
      (node (ref "C85") (pin "2") (pinfunction "2_2") (pintype "passive"))
      (node (ref "D10") (pin "E6") (pinfunction "VCC_E6") (pintype "passive"))
      (node (ref "D10") (pin "F5") (pinfunction "VCC_F5") (pintype "passive"))
      (node (ref "D10") (pin "J10") (pinfunction "VCC_J10") (pintype "passive"))
      (node (ref "D10") (pin "K9") (pinfunction "VCC_K9") (pintype "passive"))
    )
    (net (code "42") (name "Net-(C86-Pad2)") (class "Default")
      (node (ref "C86") (pin "2") (pinfunction "2_2") (pintype "passive"))
      (node (ref "C87") (pin "2") (pinfunction "2_2") (pintype "passive"))
      (node (ref "D10") (pin "C6") (pinfunction "VCCQ_C6") (pintype "passive"))
      (node (ref "D10") (pin "M4") (pinfunction "VCCQ_M4") (pintype "passive"))
      (node (ref "D10") (pin "N4") (pinfunction "VCCQ_N4") (pintype "passive"))
      (node (ref "D10") (pin "P3") (pinfunction "VCCQ_P3") (pintype "passive"))
      (node (ref "D10") (pin "P5") (pinfunction "VCCQ_P5") (pintype "passive"))
    )
    (net (code "43") (name "Net-(C91-Pad2)") (class "Default")
      (node (ref "C91") (pin "2") (pinfunction "2_2") (pintype "passive"))
      (node (ref "L5") (pin "1") (pinfunction "1_1") (pintype "passive"))
    )
    (net (code "44") (name "Net-(D9-SCK)") (class "Default")
      (node (ref "D9") (pin "13") (pinfunction "SCK_13") (pintype "input"))
      (node (ref "R36") (pin "7") (pinfunction "7_7") (pintype "passive"))
    )
    (net (code "45") (name "Net-(D9-SDI)") (class "Default")
      (node (ref "D9") (pin "14") (pinfunction "SDI_14") (pintype "input"))
      (node (ref "R36") (pin "8") (pinfunction "8_8") (pintype "passive"))
    )
    (net (code "46") (name "Net-(D9-SDO)") (class "Default")
      (node (ref "D9") (pin "1") (pinfunction "SDO_1") (pintype "output"))
      (node (ref "R36") (pin "4") (pinfunction "4_4") (pintype "passive"))
    )
    (net (code "47") (name "Net-(D9-~{CS})") (class "Default")
      (node (ref "D9") (pin "12") (pinfunction "~{CS}_12") (pintype "input"))
      (node (ref "R36") (pin "6") (pinfunction "6_6") (pintype "passive"))
    )
    (net (code "48") (name "Net-(D10A-VDDI)") (class "Default")
      (node (ref "C79") (pin "2") (pinfunction "2_2") (pintype "passive"))
      (node (ref "C80") (pin "2") (pinfunction "2_2") (pintype "passive"))
      (node (ref "D10") (pin "C2") (pinfunction "VDDI_C2") (pintype "passive"))
    )
    (net (code "49") (name "Net-(D11-FSYNC)") (class "Default")
      (node (ref "C93") (pin "2") (pinfunction "2_2") (pintype "passive"))
      (node (ref "D11") (pin "9") (pinfunction "FSYNC_9") (pintype "passive"))
      (node (ref "D13") (pin "3") (pinfunction "OUT_3") (pintype "passive"))
      (node (ref "D9") (pin "9") (pinfunction "FSYNC_9") (pintype "passive"))
    )
    (net (code "50") (name "Net-(D11-SCK)") (class "Default")
      (node (ref "D11") (pin "13") (pinfunction "SCK_13") (pintype "input"))
      (node (ref "R37") (pin "7") (pinfunction "7_7") (pintype "passive"))
    )
    (net (code "51") (name "Net-(D11-SDI)") (class "Default")
      (node (ref "D11") (pin "14") (pinfunction "SDI_14") (pintype "input"))
      (node (ref "R37") (pin "8") (pinfunction "8_8") (pintype "passive"))
    )
    (net (code "52") (name "Net-(D11-SDO)") (class "Default")
      (node (ref "D11") (pin "1") (pinfunction "SDO_1") (pintype "output"))
      (node (ref "R37") (pin "4") (pinfunction "4_4") (pintype "passive"))
    )
    (net (code "53") (name "Net-(D11-~{CS})") (class "Default")
      (node (ref "D11") (pin "12") (pinfunction "~{CS}_12") (pintype "input"))
      (node (ref "R37") (pin "6") (pinfunction "6_6") (pintype "passive"))
    )
    (net (code "54") (name "Net-(D12-ANT1)") (class "Default")
      (node (ref "D12") (pin "12") (pinfunction "ANT1_12") (pintype "passive"))
      (node (ref "L6") (pin "1") (pinfunction "1_1") (pintype "passive"))
      (node (ref "L7") (pin "2") (pinfunction "2_2") (pintype "passive"))
    )
    (net (code "55") (name "Net-(D12-ANT2)") (class "Default")
      (node (ref "D12") (pin "13") (pinfunction "ANT2_13") (pintype "passive"))
      (node (ref "L5") (pin "2") (pinfunction "2_2") (pintype "passive"))
      (node (ref "L6") (pin "2") (pinfunction "2_2") (pintype "passive"))
    )
    (net (code "56") (name "Net-(D12-DVDD)") (class "Default")
      (node (ref "C100") (pin "2") (pinfunction "2_2") (pintype "passive"))
      (node (ref "D12") (pin "19") (pinfunction "DVDD_19") (pintype "passive"))
    )
    (net (code "57") (name "Net-(D12-IREF)") (class "Default")
      (node (ref "D12") (pin "16") (pinfunction "IREF_16") (pintype "passive"))
      (node (ref "R39") (pin "2") (pinfunction "2_2") (pintype "passive"))
    )
    (net (code "58") (name "Net-(D12-VDD_PA)") (class "Default")
      (node (ref "C98") (pin "1") (pinfunction "1_1") (pintype "passive"))
      (node (ref "C99") (pin "1") (pinfunction "1_1") (pintype "passive"))
      (node (ref "D12") (pin "11") (pinfunction "VDD_PA_11") (pintype "passive"))
      (node (ref "L7") (pin "1") (pinfunction "1_1") (pintype "passive"))
    )
    (net (code "59") (name "Net-(D15-Q0)") (class "Default")
      (node (ref "D15") (pin "15") (pinfunction "Q0_15") (pintype "passive"))
      (node (ref "R41") (pin "2") (pinfunction "2_2") (pintype "passive"))
    )
    (net (code "60") (name "Net-(D15-Q1)") (class "Default")
      (node (ref "D15") (pin "1") (pinfunction "Q1_1") (pintype "passive"))
      (node (ref "R42") (pin "2") (pinfunction "2_2") (pintype "passive"))
    )
    (net (code "61") (name "Net-(D15-Q2)") (class "Default")
      (node (ref "D15") (pin "2") (pinfunction "Q2_2") (pintype "passive"))
      (node (ref "R43") (pin "2") (pinfunction "2_2") (pintype "passive"))
    )
    (net (code "62") (name "Net-(D15-Q3)") (class "Default")
      (node (ref "D15") (pin "3") (pinfunction "Q3_3") (pintype "passive"))
      (node (ref "R44") (pin "2") (pinfunction "2_2") (pintype "passive"))
    )
    (net (code "63") (name "Net-(D15-Q4)") (class "Default")
      (node (ref "D15") (pin "4") (pinfunction "Q4_4") (pintype "passive"))
      (node (ref "R45") (pin "2") (pinfunction "2_2") (pintype "passive"))
    )
    (net (code "64") (name "Net-(D15-Q5)") (class "Default")
      (node (ref "D15") (pin "5") (pinfunction "Q5_5") (pintype "passive"))
      (node (ref "R46") (pin "2") (pinfunction "2_2") (pintype "passive"))
    )
    (net (code "65") (name "Net-(D15-Q6)") (class "Default")
      (node (ref "D15") (pin "6") (pinfunction "Q6_6") (pintype "passive"))
      (node (ref "R47") (pin "2") (pinfunction "2_2") (pintype "passive"))
    )
    (net (code "66") (name "Net-(D15-Q7)") (class "Default")
      (node (ref "D15") (pin "7") (pinfunction "Q7_7") (pintype "passive"))
      (node (ref "R48") (pin "2") (pinfunction "2_2") (pintype "passive"))
    )
    (net (code "67") (name "Net-(HL1-A)") (class "Default")
      (node (ref "HL1") (pin "7") (pinfunction "A_7") (pintype "passive"))
      (node (ref "R41") (pin "1") (pinfunction "1_1") (pintype "passive"))
    )
    (net (code "68") (name "Net-(HL1-B)") (class "Default")
      (node (ref "HL1") (pin "6") (pinfunction "B_6") (pintype "passive"))
      (node (ref "R42") (pin "1") (pinfunction "1_1") (pintype "passive"))
    )
    (net (code "69") (name "Net-(HL1-C)") (class "Default")
      (node (ref "HL1") (pin "4") (pinfunction "C_4") (pintype "passive"))
      (node (ref "R43") (pin "1") (pinfunction "1_1") (pintype "passive"))
    )
    (net (code "70") (name "Net-(HL1-D)") (class "Default")
      (node (ref "HL1") (pin "2") (pinfunction "D_2") (pintype "passive"))
      (node (ref "R44") (pin "1") (pinfunction "1_1") (pintype "passive"))
    )
    (net (code "71") (name "Net-(HL1-DP)") (class "Default")
      (node (ref "HL1") (pin "5") (pinfunction "DP_5") (pintype "passive"))
      (node (ref "R48") (pin "1") (pinfunction "1_1") (pintype "passive"))
    )
    (net (code "72") (name "Net-(HL1-E)") (class "Default")
      (node (ref "HL1") (pin "1") (pinfunction "E_1") (pintype "passive"))
      (node (ref "R45") (pin "1") (pinfunction "1_1") (pintype "passive"))
    )
    (net (code "73") (name "Net-(HL1-F)") (class "Default")
      (node (ref "HL1") (pin "9") (pinfunction "F_9") (pintype "passive"))
      (node (ref "R46") (pin "1") (pinfunction "1_1") (pintype "passive"))
    )
    (net (code "74") (name "Net-(HL1-G)") (class "Default")
      (node (ref "HL1") (pin "10") (pinfunction "G_10") (pintype "passive"))
      (node (ref "R47") (pin "1") (pinfunction "1_1") (pintype "passive"))
    )
    (net (code "75") (name "Net-(X13-Antenna)") (class "Default")
      (node (ref "C91") (pin "1") (pinfunction "1_1") (pintype "passive"))
      (node (ref "C92") (pin "1") (pinfunction "1_1") (pintype "passive"))
      (node (ref "X13") (pin "1") (pinfunction "Antenna_1") (pintype "passive"))
    )
    (net (code "76") (name "unconnected-(D9-RESV-Pad2)") (class "Default")
      (node (ref "D9") (pin "2") (pinfunction "RESV_2") (pintype "passive"))
    )
    (net (code "77") (name "unconnected-(D9-RESV-Pad3)") (class "Default")
      (node (ref "D9") (pin "3") (pinfunction "RESV_3") (pintype "passive"))
    )
    (net (code "78") (name "unconnected-(D9-RESV-Pad7)") (class "Default")
      (node (ref "D9") (pin "7") (pinfunction "RESV_7") (pintype "passive"))
    )
    (net (code "79") (name "unconnected-(D9-RESV-Pad10)") (class "Default")
      (node (ref "D9") (pin "10") (pinfunction "RESV_10") (pintype "passive"))
    )
    (net (code "80") (name "unconnected-(D9-RESV-Pad11)") (class "Default")
      (node (ref "D9") (pin "11") (pinfunction "RESV_11") (pintype "passive"))
    )
    (net (code "81") (name "unconnected-(D10B-NC-PadA1)") (class "Default")
      (node (ref "D10") (pin "A1") (pinfunction "NC_A1") (pintype "passive"))
    )
    (net (code "82") (name "unconnected-(D10B-NC-PadA2)") (class "Default")
      (node (ref "D10") (pin "A2") (pinfunction "NC_A2") (pintype "passive"))
    )
    (net (code "83") (name "unconnected-(D10B-NC-PadA8)") (class "Default")
      (node (ref "D10") (pin "A8") (pinfunction "NC_A8") (pintype "passive"))
    )
    (net (code "84") (name "unconnected-(D10B-NC-PadA9)") (class "Default")
      (node (ref "D10") (pin "A9") (pinfunction "NC_A9") (pintype "passive"))
    )
    (net (code "85") (name "unconnected-(D10B-NC-PadA10)") (class "Default")
      (node (ref "D10") (pin "A10") (pinfunction "NC_A10") (pintype "passive"))
    )
    (net (code "86") (name "unconnected-(D10B-NC-PadA11)") (class "Default")
      (node (ref "D10") (pin "A11") (pinfunction "NC_A11") (pintype "passive"))
    )
    (net (code "87") (name "unconnected-(D10B-NC-PadA12)") (class "Default")
      (node (ref "D10") (pin "A12") (pinfunction "NC_A12") (pintype "passive"))
    )
    (net (code "88") (name "unconnected-(D10B-NC-PadA13)") (class "Default")
      (node (ref "D10") (pin "A13") (pinfunction "NC_A13") (pintype "passive"))
    )
    (net (code "89") (name "unconnected-(D10B-NC-PadA14)") (class "Default")
      (node (ref "D10") (pin "A14") (pinfunction "NC_A14") (pintype "passive"))
    )
    (net (code "90") (name "unconnected-(D10B-NC-PadB1)") (class "Default")
      (node (ref "D10") (pin "B1") (pinfunction "NC_B1") (pintype "passive"))
    )
    (net (code "91") (name "unconnected-(D10B-NC-PadB7)") (class "Default")
      (node (ref "D10") (pin "B7") (pinfunction "NC_B7") (pintype "passive"))
    )
    (net (code "92") (name "unconnected-(D10B-NC-PadB8)") (class "Default")
      (node (ref "D10") (pin "B8") (pinfunction "NC_B8") (pintype "passive"))
    )
    (net (code "93") (name "unconnected-(D10B-NC-PadB9)") (class "Default")
      (node (ref "D10") (pin "B9") (pinfunction "NC_B9") (pintype "passive"))
    )
    (net (code "94") (name "unconnected-(D10B-NC-PadB10)") (class "Default")
      (node (ref "D10") (pin "B10") (pinfunction "NC_B10") (pintype "passive"))
    )
    (net (code "95") (name "unconnected-(D10B-NC-PadB11)") (class "Default")
      (node (ref "D10") (pin "B11") (pinfunction "NC_B11") (pintype "passive"))
    )
    (net (code "96") (name "unconnected-(D10B-NC-PadB12)") (class "Default")
      (node (ref "D10") (pin "B12") (pinfunction "NC_B12") (pintype "passive"))
    )
    (net (code "97") (name "unconnected-(D10B-NC-PadB13)") (class "Default")
      (node (ref "D10") (pin "B13") (pinfunction "NC_B13") (pintype "passive"))
    )
    (net (code "98") (name "unconnected-(D10B-NC-PadB14)") (class "Default")
      (node (ref "D10") (pin "B14") (pinfunction "NC_B14") (pintype "passive"))
    )
    (net (code "99") (name "unconnected-(D10B-RFU-PadA7)") (class "Default")
      (node (ref "D10") (pin "A7") (pinfunction "RFU_A7") (pintype "passive"))
    )
    (net (code "100") (name "unconnected-(D10B-RFU-PadE5)") (class "Default")
      (node (ref "D10") (pin "E5") (pinfunction "RFU_E5") (pintype "passive"))
    )
    (net (code "101") (name "unconnected-(D10B-RFU-PadE8)") (class "Default")
      (node (ref "D10") (pin "E8") (pinfunction "RFU_E8") (pintype "passive"))
    )
    (net (code "102") (name "unconnected-(D10B-RFU-PadE9)") (class "Default")
      (node (ref "D10") (pin "E9") (pinfunction "RFU_E9") (pintype "passive"))
    )
    (net (code "103") (name "unconnected-(D10B-RFU-PadE10)") (class "Default")
      (node (ref "D10") (pin "E10") (pinfunction "RFU_E10") (pintype "passive"))
    )
    (net (code "104") (name "unconnected-(D10B-RFU-PadF10)") (class "Default")
      (node (ref "D10") (pin "F10") (pinfunction "RFU_F10") (pintype "passive"))
    )
    (net (code "105") (name "unconnected-(D10B-RFU-PadG10)") (class "Default")
      (node (ref "D10") (pin "G10") (pinfunction "RFU_G10") (pintype "passive"))
    )
    (net (code "106") (name "unconnected-(D10B-RFU-PadK6)") (class "Default")
      (node (ref "D10") (pin "K6") (pinfunction "RFU_K6") (pintype "passive"))
    )
    (net (code "107") (name "unconnected-(D10B-RFU-PadK7)") (class "Default")
      (node (ref "D10") (pin "K7") (pinfunction "RFU_K7") (pintype "passive"))
    )
    (net (code "108") (name "unconnected-(D10B-RFU-PadK10)") (class "Default")
      (node (ref "D10") (pin "K10") (pinfunction "RFU_K10") (pintype "passive"))
    )
    (net (code "109") (name "unconnected-(D10B-RFU-PadP7)") (class "Default")
      (node (ref "D10") (pin "P7") (pinfunction "RFU_P7") (pintype "passive"))
    )
    (net (code "110") (name "unconnected-(D10B-RFU-PadP10)") (class "Default")
      (node (ref "D10") (pin "P10") (pinfunction "RFU_P10") (pintype "passive"))
    )
    (net (code "111") (name "unconnected-(D10C-NC-PadC1)") (class "Default")
      (node (ref "D10") (pin "C1") (pinfunction "NC_C1") (pintype "passive"))
    )
    (net (code "112") (name "unconnected-(D10C-NC-PadC3)") (class "Default")
      (node (ref "D10") (pin "C3") (pinfunction "NC_C3") (pintype "passive"))
    )
    (net (code "113") (name "unconnected-(D10C-NC-PadC5)") (class "Default")
      (node (ref "D10") (pin "C5") (pinfunction "NC_C5") (pintype "passive"))
    )
    (net (code "114") (name "unconnected-(D10C-NC-PadC7)") (class "Default")
      (node (ref "D10") (pin "C7") (pinfunction "NC_C7") (pintype "passive"))
    )
    (net (code "115") (name "unconnected-(D10C-NC-PadC8)") (class "Default")
      (node (ref "D10") (pin "C8") (pinfunction "NC_C8") (pintype "passive"))
    )
    (net (code "116") (name "unconnected-(D10C-NC-PadC9)") (class "Default")
      (node (ref "D10") (pin "C9") (pinfunction "NC_C9") (pintype "passive"))
    )
    (net (code "117") (name "unconnected-(D10C-NC-PadC10)") (class "Default")
      (node (ref "D10") (pin "C10") (pinfunction "NC_C10") (pintype "passive"))
    )
    (net (code "118") (name "unconnected-(D10C-NC-PadC11)") (class "Default")
      (node (ref "D10") (pin "C11") (pinfunction "NC_C11") (pintype "passive"))
    )
    (net (code "119") (name "unconnected-(D10C-NC-PadC12)") (class "Default")
      (node (ref "D10") (pin "C12") (pinfunction "NC_C12") (pintype "passive"))
    )
    (net (code "120") (name "unconnected-(D10C-NC-PadC13)") (class "Default")
      (node (ref "D10") (pin "C13") (pinfunction "NC_C13") (pintype "passive"))
    )
    (net (code "121") (name "unconnected-(D10C-NC-PadC14)") (class "Default")
      (node (ref "D10") (pin "C14") (pinfunction "NC_C14") (pintype "passive"))
    )
    (net (code "122") (name "unconnected-(D10C-NC-PadD1)") (class "Default")
      (node (ref "D10") (pin "D1") (pinfunction "NC_D1") (pintype "passive"))
    )
    (net (code "123") (name "unconnected-(D10C-NC-PadD2)") (class "Default")
      (node (ref "D10") (pin "D2") (pinfunction "NC_D2") (pintype "passive"))
    )
    (net (code "124") (name "unconnected-(D10C-NC-PadD3)") (class "Default")
      (node (ref "D10") (pin "D3") (pinfunction "NC_D3") (pintype "passive"))
    )
    (net (code "125") (name "unconnected-(D10C-NC-PadD4)") (class "Default")
      (node (ref "D10") (pin "D4") (pinfunction "NC_D4") (pintype "passive"))
    )
    (net (code "126") (name "unconnected-(D10C-NC-PadD12)") (class "Default")
      (node (ref "D10") (pin "D12") (pinfunction "NC_D12") (pintype "passive"))
    )
    (net (code "127") (name "unconnected-(D10C-NC-PadD13)") (class "Default")
      (node (ref "D10") (pin "D13") (pinfunction "NC_D13") (pintype "passive"))
    )
    (net (code "128") (name "unconnected-(D10C-NC-PadD14)") (class "Default")
      (node (ref "D10") (pin "D14") (pinfunction "NC_D14") (pintype "passive"))
    )
    (net (code "129") (name "unconnected-(D10C-NC-PadE1)") (class "Default")
      (node (ref "D10") (pin "E1") (pinfunction "NC_E1") (pintype "passive"))
    )
    (net (code "130") (name "unconnected-(D10C-NC-PadE2)") (class "Default")
      (node (ref "D10") (pin "E2") (pinfunction "NC_E2") (pintype "passive"))
    )
    (net (code "131") (name "unconnected-(D10C-NC-PadE3)") (class "Default")
      (node (ref "D10") (pin "E3") (pinfunction "NC_E3") (pintype "passive"))
    )
    (net (code "132") (name "unconnected-(D10C-NC-PadE12)") (class "Default")
      (node (ref "D10") (pin "E12") (pinfunction "NC_E12") (pintype "passive"))
    )
    (net (code "133") (name "unconnected-(D10C-NC-PadE13)") (class "Default")
      (node (ref "D10") (pin "E13") (pinfunction "NC_E13") (pintype "passive"))
    )
    (net (code "134") (name "unconnected-(D10C-NC-PadE14)") (class "Default")
      (node (ref "D10") (pin "E14") (pinfunction "NC_E14") (pintype "passive"))
    )
    (net (code "135") (name "unconnected-(D10C-NC-PadF1)") (class "Default")
      (node (ref "D10") (pin "F1") (pinfunction "NC_F1") (pintype "passive"))
    )
    (net (code "136") (name "unconnected-(D10C-NC-PadF2)") (class "Default")
      (node (ref "D10") (pin "F2") (pinfunction "NC_F2") (pintype "passive"))
    )
    (net (code "137") (name "unconnected-(D10C-NC-PadF3)") (class "Default")
      (node (ref "D10") (pin "F3") (pinfunction "NC_F3") (pintype "passive"))
    )
    (net (code "138") (name "unconnected-(D10C-NC-PadF12)") (class "Default")
      (node (ref "D10") (pin "F12") (pinfunction "NC_F12") (pintype "passive"))
    )
    (net (code "139") (name "unconnected-(D10C-NC-PadF13)") (class "Default")
      (node (ref "D10") (pin "F13") (pinfunction "NC_F13") (pintype "passive"))
    )
    (net (code "140") (name "unconnected-(D10C-NC-PadF14)") (class "Default")
      (node (ref "D10") (pin "F14") (pinfunction "NC_F14") (pintype "passive"))
    )
    (net (code "141") (name "unconnected-(D10D-NC-PadG1)") (class "Default")
      (node (ref "D10") (pin "G1") (pinfunction "NC_G1") (pintype "passive"))
    )
    (net (code "142") (name "unconnected-(D10D-NC-PadG2)") (class "Default")
      (node (ref "D10") (pin "G2") (pinfunction "NC_G2") (pintype "passive"))
    )
    (net (code "143") (name "unconnected-(D10D-NC-PadG3)") (class "Default")
      (node (ref "D10") (pin "G3") (pinfunction "NC_G3") (pintype "passive"))
    )
    (net (code "144") (name "unconnected-(D10D-NC-PadG12)") (class "Default")
      (node (ref "D10") (pin "G12") (pinfunction "NC_G12") (pintype "passive"))
    )
    (net (code "145") (name "unconnected-(D10D-NC-PadG13)") (class "Default")
      (node (ref "D10") (pin "G13") (pinfunction "NC_G13") (pintype "passive"))
    )
    (net (code "146") (name "unconnected-(D10D-NC-PadG14)") (class "Default")
      (node (ref "D10") (pin "G14") (pinfunction "NC_G14") (pintype "passive"))
    )
    (net (code "147") (name "unconnected-(D10D-NC-PadH1)") (class "Default")
      (node (ref "D10") (pin "H1") (pinfunction "NC_H1") (pintype "passive"))
    )
    (net (code "148") (name "unconnected-(D10D-NC-PadH2)") (class "Default")
      (node (ref "D10") (pin "H2") (pinfunction "NC_H2") (pintype "passive"))
    )
    (net (code "149") (name "unconnected-(D10D-NC-PadH3)") (class "Default")
      (node (ref "D10") (pin "H3") (pinfunction "NC_H3") (pintype "passive"))
    )
    (net (code "150") (name "unconnected-(D10D-NC-PadH12)") (class "Default")
      (node (ref "D10") (pin "H12") (pinfunction "NC_H12") (pintype "passive"))
    )
    (net (code "151") (name "unconnected-(D10D-NC-PadH13)") (class "Default")
      (node (ref "D10") (pin "H13") (pinfunction "NC_H13") (pintype "passive"))
    )
    (net (code "152") (name "unconnected-(D10D-NC-PadH14)") (class "Default")
      (node (ref "D10") (pin "H14") (pinfunction "NC_H14") (pintype "passive"))
    )
    (net (code "153") (name "unconnected-(D10D-NC-PadJ1)") (class "Default")
      (node (ref "D10") (pin "J1") (pinfunction "NC_J1") (pintype "passive"))
    )
    (net (code "154") (name "unconnected-(D10D-NC-PadJ2)") (class "Default")
      (node (ref "D10") (pin "J2") (pinfunction "NC_J2") (pintype "passive"))
    )
    (net (code "155") (name "unconnected-(D10D-NC-PadJ3)") (class "Default")
      (node (ref "D10") (pin "J3") (pinfunction "NC_J3") (pintype "passive"))
    )
    (net (code "156") (name "unconnected-(D10D-NC-PadJ12)") (class "Default")
      (node (ref "D10") (pin "J12") (pinfunction "NC_J12") (pintype "passive"))
    )
    (net (code "157") (name "unconnected-(D10D-NC-PadJ13)") (class "Default")
      (node (ref "D10") (pin "J13") (pinfunction "NC_J13") (pintype "passive"))
    )
    (net (code "158") (name "unconnected-(D10D-NC-PadJ14)") (class "Default")
      (node (ref "D10") (pin "J14") (pinfunction "NC_J14") (pintype "passive"))
    )
    (net (code "159") (name "unconnected-(D10D-NC-PadK1)") (class "Default")
      (node (ref "D10") (pin "K1") (pinfunction "NC_K1") (pintype "passive"))
    )
    (net (code "160") (name "unconnected-(D10D-NC-PadK2)") (class "Default")
      (node (ref "D10") (pin "K2") (pinfunction "NC_K2") (pintype "passive"))
    )
    (net (code "161") (name "unconnected-(D10D-NC-PadK3)") (class "Default")
      (node (ref "D10") (pin "K3") (pinfunction "NC_K3") (pintype "passive"))
    )
    (net (code "162") (name "unconnected-(D10D-NC-PadK12)") (class "Default")
      (node (ref "D10") (pin "K12") (pinfunction "NC_K12") (pintype "passive"))
    )
    (net (code "163") (name "unconnected-(D10D-NC-PadK13)") (class "Default")
      (node (ref "D10") (pin "K13") (pinfunction "NC_K13") (pintype "passive"))
    )
    (net (code "164") (name "unconnected-(D10D-NC-PadK14)") (class "Default")
      (node (ref "D10") (pin "K14") (pinfunction "NC_K14") (pintype "passive"))
    )
    (net (code "165") (name "unconnected-(D10D-NC-PadL1)") (class "Default")
      (node (ref "D10") (pin "L1") (pinfunction "NC_L1") (pintype "passive"))
    )
    (net (code "166") (name "unconnected-(D10D-NC-PadL2)") (class "Default")
      (node (ref "D10") (pin "L2") (pinfunction "NC_L2") (pintype "passive"))
    )
    (net (code "167") (name "unconnected-(D10D-NC-PadL3)") (class "Default")
      (node (ref "D10") (pin "L3") (pinfunction "NC_L3") (pintype "passive"))
    )
    (net (code "168") (name "unconnected-(D10D-NC-PadL12)") (class "Default")
      (node (ref "D10") (pin "L12") (pinfunction "NC_L12") (pintype "passive"))
    )
    (net (code "169") (name "unconnected-(D10D-NC-PadL13)") (class "Default")
      (node (ref "D10") (pin "L13") (pinfunction "NC_L13") (pintype "passive"))
    )
    (net (code "170") (name "unconnected-(D10D-NC-PadL14)") (class "Default")
      (node (ref "D10") (pin "L14") (pinfunction "NC_L14") (pintype "passive"))
    )
    (net (code "171") (name "unconnected-(D10E-NC-PadM1)") (class "Default")
      (node (ref "D10") (pin "M1") (pinfunction "NC_M1") (pintype "passive"))
    )
    (net (code "172") (name "unconnected-(D10E-NC-PadM2)") (class "Default")
      (node (ref "D10") (pin "M2") (pinfunction "NC_M2") (pintype "passive"))
    )
    (net (code "173") (name "unconnected-(D10E-NC-PadM3)") (class "Default")
      (node (ref "D10") (pin "M3") (pinfunction "NC_M3") (pintype "passive"))
    )
    (net (code "174") (name "unconnected-(D10E-NC-PadM7)") (class "Default")
      (node (ref "D10") (pin "M7") (pinfunction "NC_M7") (pintype "passive"))
    )
    (net (code "175") (name "unconnected-(D10E-NC-PadM8)") (class "Default")
      (node (ref "D10") (pin "M8") (pinfunction "NC_M8") (pintype "passive"))
    )
    (net (code "176") (name "unconnected-(D10E-NC-PadM9)") (class "Default")
      (node (ref "D10") (pin "M9") (pinfunction "NC_M9") (pintype "passive"))
    )
    (net (code "177") (name "unconnected-(D10E-NC-PadM10)") (class "Default")
      (node (ref "D10") (pin "M10") (pinfunction "NC_M10") (pintype "passive"))
    )
    (net (code "178") (name "unconnected-(D10E-NC-PadM11)") (class "Default")
      (node (ref "D10") (pin "M11") (pinfunction "NC_M11") (pintype "passive"))
    )
    (net (code "179") (name "unconnected-(D10E-NC-PadM12)") (class "Default")
      (node (ref "D10") (pin "M12") (pinfunction "NC_M12") (pintype "passive"))
    )
    (net (code "180") (name "unconnected-(D10E-NC-PadM13)") (class "Default")
      (node (ref "D10") (pin "M13") (pinfunction "NC_M13") (pintype "passive"))
    )
    (net (code "181") (name "unconnected-(D10E-NC-PadM14)") (class "Default")
      (node (ref "D10") (pin "M14") (pinfunction "NC_M14") (pintype "passive"))
    )
    (net (code "182") (name "unconnected-(D10E-NC-PadN1)") (class "Default")
      (node (ref "D10") (pin "N1") (pinfunction "NC_N1") (pintype "passive"))
    )
    (net (code "183") (name "unconnected-(D10E-NC-PadN3)") (class "Default")
      (node (ref "D10") (pin "N3") (pinfunction "NC_N3") (pintype "passive"))
    )
    (net (code "184") (name "unconnected-(D10E-NC-PadN6)") (class "Default")
      (node (ref "D10") (pin "N6") (pinfunction "NC_N6") (pintype "passive"))
    )
    (net (code "185") (name "unconnected-(D10E-NC-PadN7)") (class "Default")
      (node (ref "D10") (pin "N7") (pinfunction "NC_N7") (pintype "passive"))
    )
    (net (code "186") (name "unconnected-(D10E-NC-PadN8)") (class "Default")
      (node (ref "D10") (pin "N8") (pinfunction "NC_N8") (pintype "passive"))
    )
    (net (code "187") (name "unconnected-(D10E-NC-PadN9)") (class "Default")
      (node (ref "D10") (pin "N9") (pinfunction "NC_N9") (pintype "passive"))
    )
    (net (code "188") (name "unconnected-(D10E-NC-PadN10)") (class "Default")
      (node (ref "D10") (pin "N10") (pinfunction "NC_N10") (pintype "passive"))
    )
    (net (code "189") (name "unconnected-(D10E-NC-PadN11)") (class "Default")
      (node (ref "D10") (pin "N11") (pinfunction "NC_N11") (pintype "passive"))
    )
    (net (code "190") (name "unconnected-(D10E-NC-PadN12)") (class "Default")
      (node (ref "D10") (pin "N12") (pinfunction "NC_N12") (pintype "passive"))
    )
    (net (code "191") (name "unconnected-(D10E-NC-PadN13)") (class "Default")
      (node (ref "D10") (pin "N13") (pinfunction "NC_N13") (pintype "passive"))
    )
    (net (code "192") (name "unconnected-(D10E-NC-PadN14)") (class "Default")
      (node (ref "D10") (pin "N14") (pinfunction "NC_N14") (pintype "passive"))
    )
    (net (code "193") (name "unconnected-(D10E-NC-PadP1)") (class "Default")
      (node (ref "D10") (pin "P1") (pinfunction "NC_P1") (pintype "passive"))
    )
    (net (code "194") (name "unconnected-(D10E-NC-PadP2)") (class "Default")
      (node (ref "D10") (pin "P2") (pinfunction "NC_P2") (pintype "passive"))
    )
    (net (code "195") (name "unconnected-(D10E-NC-PadP8)") (class "Default")
      (node (ref "D10") (pin "P8") (pinfunction "NC_P8") (pintype "passive"))
    )
    (net (code "196") (name "unconnected-(D10E-NC-PadP9)") (class "Default")
      (node (ref "D10") (pin "P9") (pinfunction "NC_P9") (pintype "passive"))
    )
    (net (code "197") (name "unconnected-(D10E-NC-PadP11)") (class "Default")
      (node (ref "D10") (pin "P11") (pinfunction "NC_P11") (pintype "passive"))
    )
    (net (code "198") (name "unconnected-(D10E-NC-PadP12)") (class "Default")
      (node (ref "D10") (pin "P12") (pinfunction "NC_P12") (pintype "passive"))
    )
    (net (code "199") (name "unconnected-(D10E-NC-PadP13)") (class "Default")
      (node (ref "D10") (pin "P13") (pinfunction "NC_P13") (pintype "passive"))
    )
    (net (code "200") (name "unconnected-(D10E-NC-PadP14)") (class "Default")
      (node (ref "D10") (pin "P14") (pinfunction "NC_P14") (pintype "passive"))
    )
    (net (code "201") (name "unconnected-(D11-RESV-Pad2)") (class "Default")
      (node (ref "D11") (pin "2") (pinfunction "RESV_2") (pintype "passive"))
    )
    (net (code "202") (name "unconnected-(D11-RESV-Pad3)") (class "Default")
      (node (ref "D11") (pin "3") (pinfunction "RESV_3") (pintype "passive"))
    )
    (net (code "203") (name "unconnected-(D11-RESV-Pad7)") (class "Default")
      (node (ref "D11") (pin "7") (pinfunction "RESV_7") (pintype "passive"))
    )
    (net (code "204") (name "unconnected-(D11-RESV-Pad10)") (class "Default")
      (node (ref "D11") (pin "10") (pinfunction "RESV_10") (pintype "passive"))
    )
    (net (code "205") (name "unconnected-(D11-RESV-Pad11)") (class "Default")
      (node (ref "D11") (pin "11") (pinfunction "RESV_11") (pintype "passive"))
    )
    (net (code "206") (name "unconnected-(D15-Q7S-Pad9)") (class "Default")
      (node (ref "D15") (pin "9") (pinfunction "Q7S_9") (pintype "passive"))
    )
  )
)
